# SCH_555-Circuit_2025-11-01.net
KiCad netlist of a schematic drawn in EasyEDA
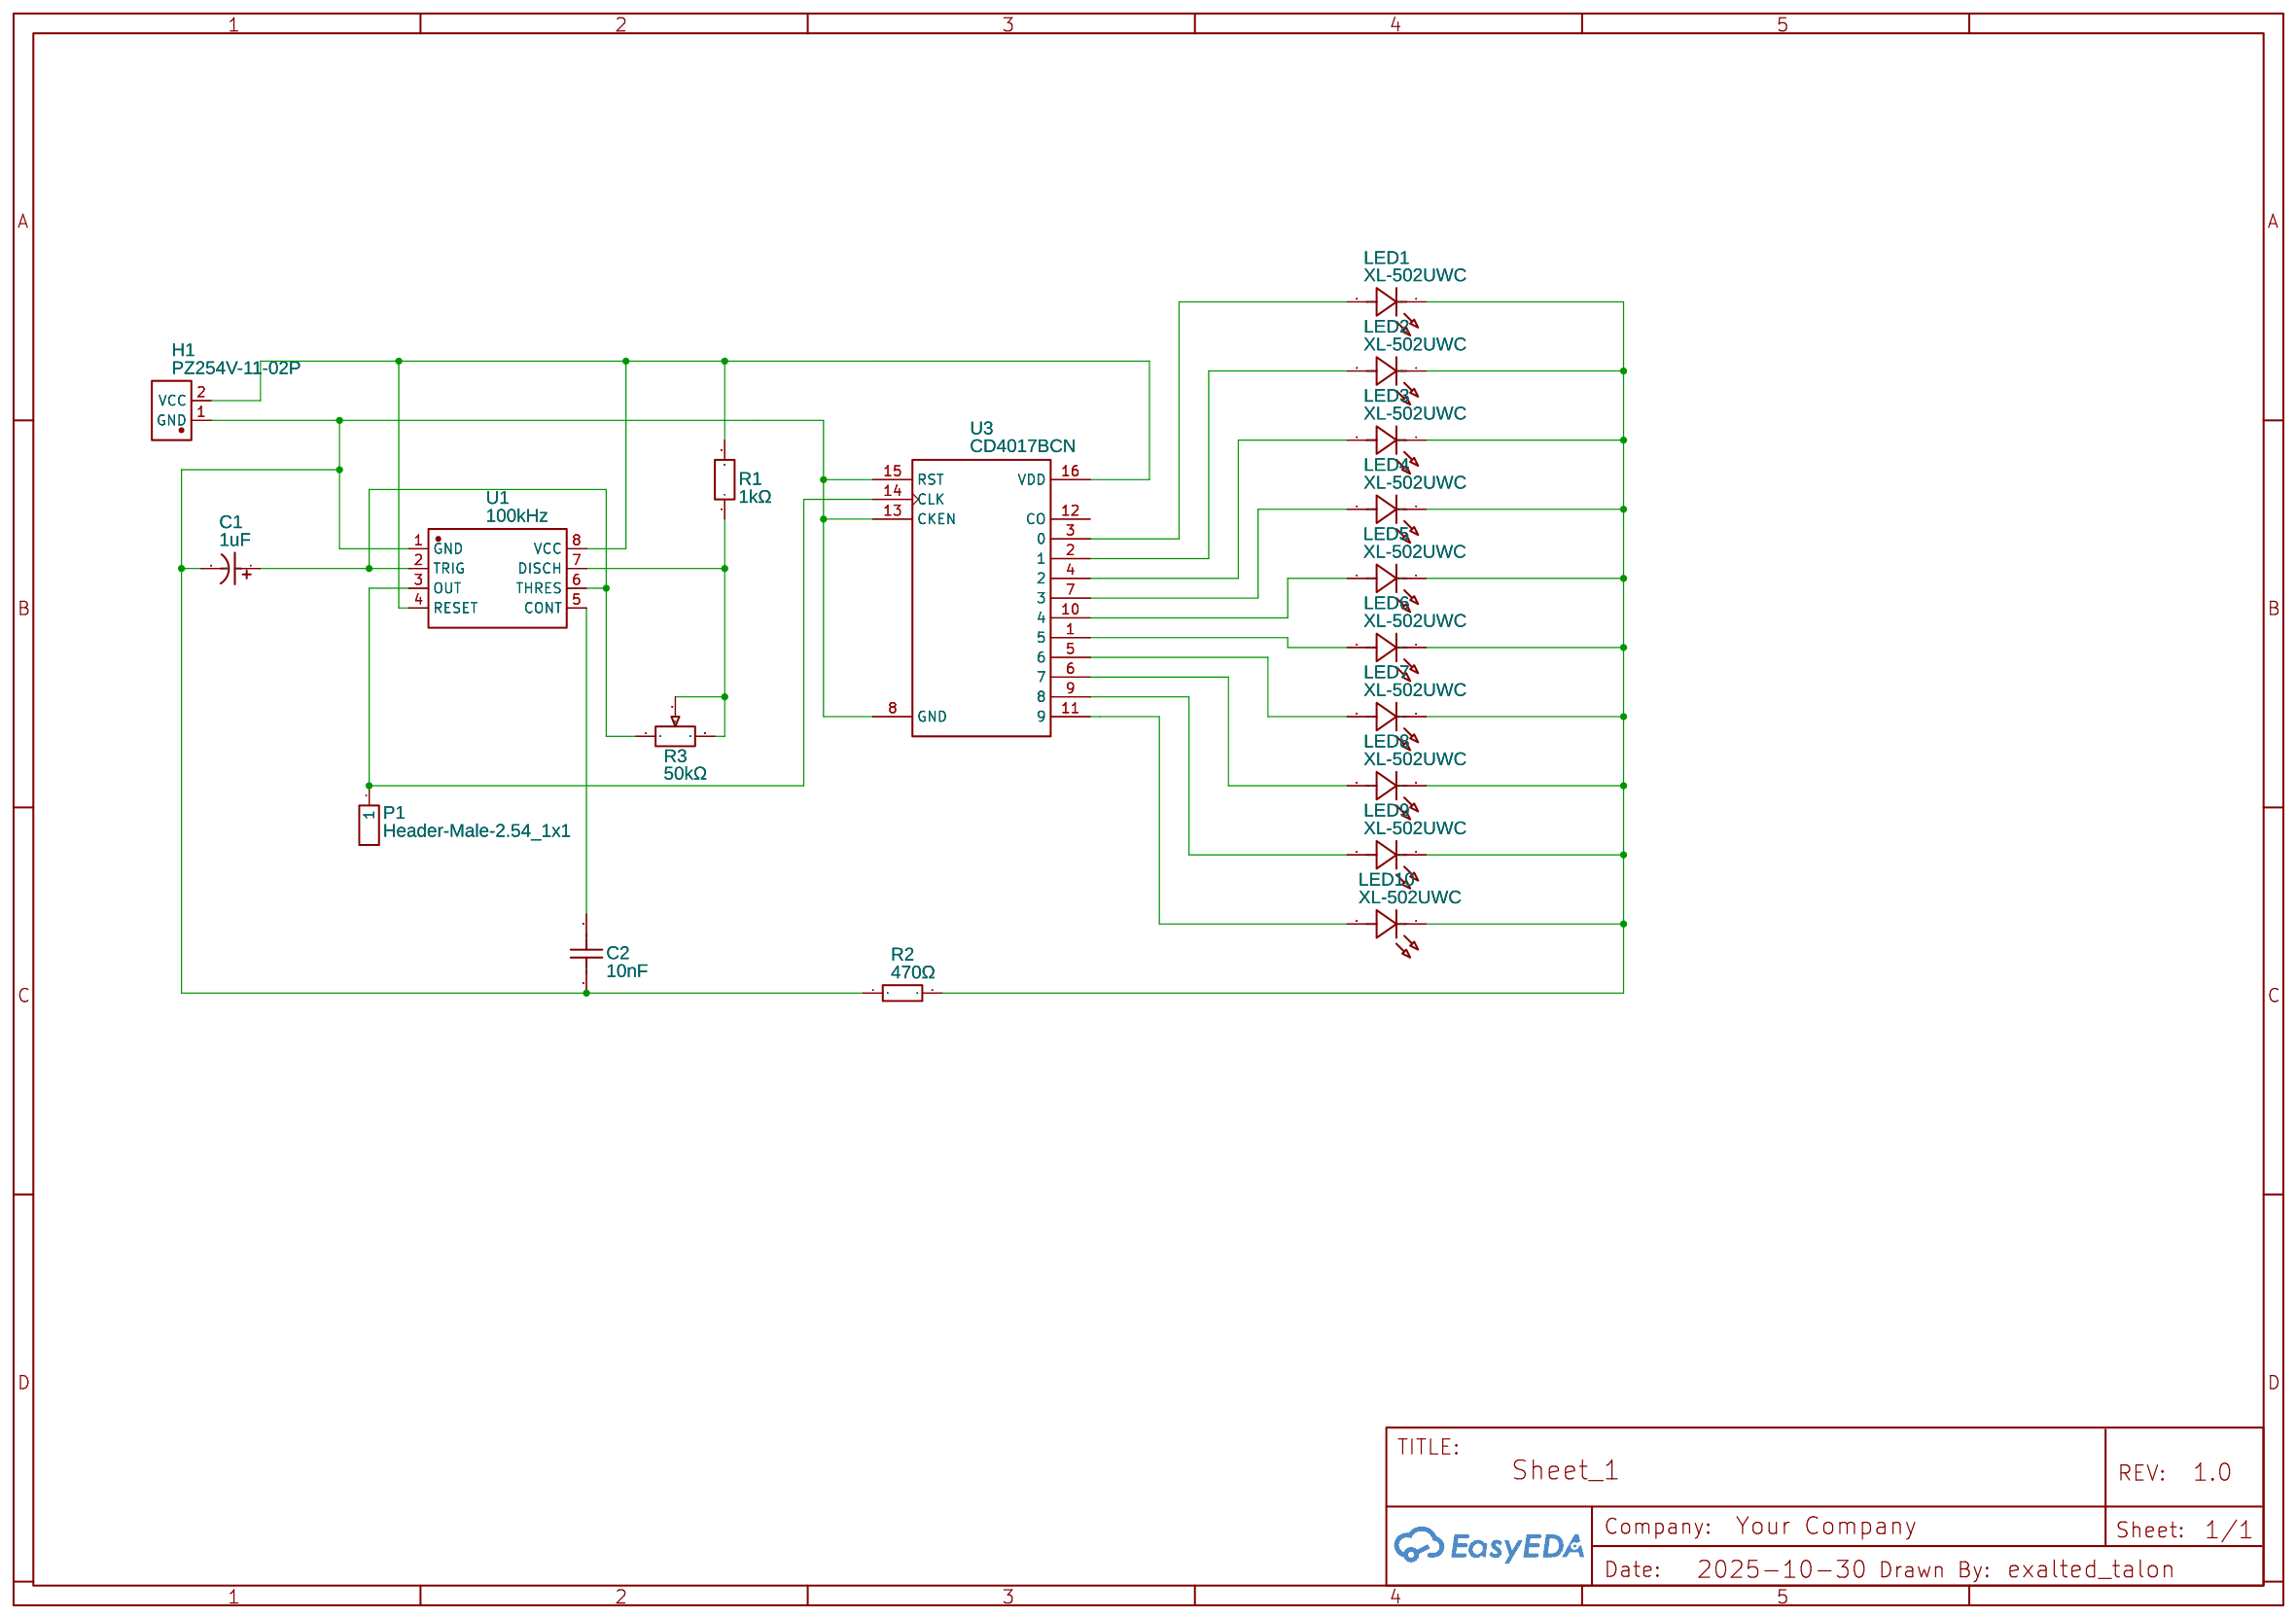
[diagram p0: schematic sheet]

(export (version "E")
  (design (tool "Eeschema 10.0.6"))
  (components
    (comp (ref "C1")
      (value "1uF")
      (fields (field (name "Manufacturer Part") "KF010M050C110A") (field (name "Manufacturer") "CapXon(丰宾)"))
      (libsource (lib "") (part "KF010M050C110A"))
    )
    (comp (ref "C2")
      (value "10nF")
      (fields (field (name "Manufacturer Part") "N09F1B103MN0B0S0N0") (field (name "Manufacturer") "STE(松田)"))
      (libsource (lib "") (part "N09F1B103MN0B0S0N0"))
    )
    (comp (ref "H1")
      (value "PZ254V-11-02P")
      (fields (field (name "Manufacturer") "XFCN(兴飞)"))
      (libsource (lib "") (part "PZ254V-11-02P"))
    )
    (comp (ref "LED1")
      (value "XL-502UWC")
      (fields (field (name "Manufacturer") "XINGLIGHT(成兴光)"))
      (libsource (lib "") (part "XL-502UWC"))
    )
    (comp (ref "LED2")
      (value "XL-502UWC")
      (fields (field (name "Manufacturer") "XINGLIGHT(成兴光)"))
      (libsource (lib "") (part "XL-502UWC"))
    )
    (comp (ref "LED3")
      (value "XL-502UWC")
      (fields (field (name "Manufacturer") "XINGLIGHT(成兴光)"))
      (libsource (lib "") (part "XL-502UWC"))
    )
    (comp (ref "LED4")
      (value "XL-502UWC")
      (fields (field (name "Manufacturer") "XINGLIGHT(成兴光)"))
      (libsource (lib "") (part "XL-502UWC"))
    )
    (comp (ref "LED5")
      (value "XL-502UWC")
      (fields (field (name "Manufacturer") "XINGLIGHT(成兴光)"))
      (libsource (lib "") (part "XL-502UWC"))
    )
    (comp (ref "LED6")
      (value "XL-502UWC")
      (fields (field (name "Manufacturer") "XINGLIGHT(成兴光)"))
      (libsource (lib "") (part "XL-502UWC"))
    )
    (comp (ref "LED7")
      (value "XL-502UWC")
      (fields (field (name "Manufacturer") "XINGLIGHT(成兴光)"))
      (libsource (lib "") (part "XL-502UWC"))
    )
    (comp (ref "LED8")
      (value "XL-502UWC")
      (fields (field (name "Manufacturer") "XINGLIGHT(成兴光)"))
      (libsource (lib "") (part "XL-502UWC"))
    )
    (comp (ref "LED9")
      (value "XL-502UWC")
      (fields (field (name "Manufacturer") "XINGLIGHT(成兴光)"))
      (libsource (lib "") (part "XL-502UWC"))
    )
    (comp (ref "LED10")
      (value "XL-502UWC")
      (fields (field (name "Manufacturer") "XINGLIGHT(成兴光)"))
      (libsource (lib "") (part "XL-502UWC"))
    )
    (comp (ref "P1")
      (value "Header-Male-2.54_1x1")
      (fields (field (name "Manufacturer Part") "2.54-1*1P针") (field (name "Manufacturer") "BOOMELE(博穆精密)"))
      (libsource (lib "") (part "Header-Male-2.54_1x1"))
    )
    (comp (ref "R1")
      (value "1kΩ")
      (fields (field (name "Manufacturer Part") "MF1/4W-1KΩ±1%T52") (field (name "Manufacturer") "华星机电"))
      (libsource (lib "") (part "MF1/4W-1KΩ±1%T52"))
    )
    (comp (ref "R2")
      (value "470Ω")
      (fields
        (field (name "Manufacturer Part") "MFR0W4F4700A50")
        (field (name "Manufacturer") "UNI-ROYAL(厚声)")
      )
      (libsource (lib "") (part "MFR0W4F4700A50"))
    )
    (comp (ref "R3")
      (value "50kΩ")
      (fields (field (name "Manufacturer Part") "3296X-1-503") (field (name "Manufacturer") "BOCHEN(博晨)"))
      (libsource (lib "") (part "3296X-1-503_C118912"))
    )
    (comp (ref "U1")
      (value "100kHz")
      (fields (field (name "Manufacturer Part") "NE555P") (field (name "Manufacturer") "TI(德州仪器)"))
      (libsource (lib "") (part "NE555P"))
    )
    (comp (ref "U3") (value "CD4017BCN") (libsource (lib "") (part "CD4017BCN")))
  )
  (nets
    (net (code "1") (name "Net-(H1-GND)") (class "Default")
      (node (ref "C1") (pin "2") (pinfunction "2_2") (pintype "input"))
      (node (ref "C2") (pin "1") (pinfunction "1_1") (pintype "unspecified"))
      (node (ref "H1") (pin "1") (pinfunction "GND_1") (pintype "unspecified"))
      (node (ref "R2") (pin "1") (pinfunction "1_1") (pintype "input"))
      (node (ref "U1") (pin "1") (pinfunction "GND_1") (pintype "unspecified"))
      (node (ref "U3") (pin "13") (pinfunction "CKEN_13") (pintype "unspecified"))
      (node (ref "U3") (pin "15") (pinfunction "RST_15") (pintype "unspecified"))
      (node (ref "U3") (pin "8") (pinfunction "GND_8") (pintype "passive"))
    )
    (net (code "2") (name "Net-(H1-VCC)") (class "Default")
      (node (ref "H1") (pin "2") (pinfunction "VCC_2") (pintype "unspecified"))
      (node (ref "R1") (pin "2") (pinfunction "2_2") (pintype "unspecified"))
      (node (ref "U1") (pin "4") (pinfunction "RESET_4") (pintype "unspecified"))
      (node (ref "U1") (pin "8") (pinfunction "VCC_8") (pintype "unspecified"))
      (node (ref "U3") (pin "16") (pinfunction "VDD_16") (pintype "passive"))
    )
    (net (code "3") (name "Net-(LED1-A)") (class "Default")
      (node (ref "LED1") (pin "2") (pinfunction "A_2") (pintype "unspecified"))
      (node (ref "U3") (pin "3") (pinfunction "0_3") (pintype "output"))
    )
    (net (code "4") (name "Net-(LED1-K)") (class "Default")
      (node (ref "LED1") (pin "1") (pinfunction "K_1") (pintype "unspecified"))
      (node (ref "LED10") (pin "1") (pinfunction "K_1") (pintype "unspecified"))
      (node (ref "LED2") (pin "1") (pinfunction "K_1") (pintype "unspecified"))
      (node (ref "LED3") (pin "1") (pinfunction "K_1") (pintype "unspecified"))
      (node (ref "LED4") (pin "1") (pinfunction "K_1") (pintype "unspecified"))
      (node (ref "LED5") (pin "1") (pinfunction "K_1") (pintype "unspecified"))
      (node (ref "LED6") (pin "1") (pinfunction "K_1") (pintype "unspecified"))
      (node (ref "LED7") (pin "1") (pinfunction "K_1") (pintype "unspecified"))
      (node (ref "LED8") (pin "1") (pinfunction "K_1") (pintype "unspecified"))
      (node (ref "LED9") (pin "1") (pinfunction "K_1") (pintype "unspecified"))
      (node (ref "R2") (pin "2") (pinfunction "2_2") (pintype "input"))
    )
    (net (code "5") (name "Net-(LED2-A)") (class "Default")
      (node (ref "LED2") (pin "2") (pinfunction "A_2") (pintype "unspecified"))
      (node (ref "U3") (pin "2") (pinfunction "1_2") (pintype "output"))
    )
    (net (code "6") (name "Net-(LED3-A)") (class "Default")
      (node (ref "LED3") (pin "2") (pinfunction "A_2") (pintype "unspecified"))
      (node (ref "U3") (pin "4") (pinfunction "2_4") (pintype "output"))
    )
    (net (code "7") (name "Net-(LED4-A)") (class "Default")
      (node (ref "LED4") (pin "2") (pinfunction "A_2") (pintype "unspecified"))
      (node (ref "U3") (pin "7") (pinfunction "3_7") (pintype "output"))
    )
    (net (code "8") (name "Net-(LED5-A)") (class "Default")
      (node (ref "LED5") (pin "2") (pinfunction "A_2") (pintype "unspecified"))
      (node (ref "U3") (pin "10") (pinfunction "4_10") (pintype "output"))
    )
    (net (code "9") (name "Net-(LED6-A)") (class "Default")
      (node (ref "LED6") (pin "2") (pinfunction "A_2") (pintype "unspecified"))
      (node (ref "U3") (pin "1") (pinfunction "5_1") (pintype "output"))
    )
    (net (code "10") (name "Net-(LED7-A)") (class "Default")
      (node (ref "LED7") (pin "2") (pinfunction "A_2") (pintype "unspecified"))
      (node (ref "U3") (pin "5") (pinfunction "6_5") (pintype "output"))
    )
    (net (code "11") (name "Net-(LED8-A)") (class "Default")
      (node (ref "LED8") (pin "2") (pinfunction "A_2") (pintype "unspecified"))
      (node (ref "U3") (pin "6") (pinfunction "7_6") (pintype "output"))
    )
    (net (code "12") (name "Net-(LED9-A)") (class "Default")
      (node (ref "LED9") (pin "2") (pinfunction "A_2") (pintype "unspecified"))
      (node (ref "U3") (pin "9") (pinfunction "8_9") (pintype "output"))
    )
    (net (code "13") (name "Net-(LED10-A)") (class "Default")
      (node (ref "LED10") (pin "2") (pinfunction "A_2") (pintype "unspecified"))
      (node (ref "U3") (pin "11") (pinfunction "9_11") (pintype "output"))
    )
    (net (code "14") (name "Net-(U1-CONT)") (class "Default")
      (node (ref "C2") (pin "2") (pinfunction "2_2") (pintype "unspecified"))
      (node (ref "U1") (pin "5") (pinfunction "CONT_5") (pintype "unspecified"))
    )
    (net (code "15") (name "Net-(U1-DISCH)") (class "Default")
      (node (ref "R1") (pin "1") (pinfunction "1_1") (pintype "unspecified"))
      (node (ref "R3") (pin "2") (pinfunction "2_2") (pintype "input"))
      (node (ref "R3") (pin "3") (pinfunction "3_3") (pintype "input"))
      (node (ref "U1") (pin "7") (pinfunction "DISCH_7") (pintype "unspecified"))
    )
    (net (code "16") (name "Net-(U1-OUT)") (class "Default")
      (node (ref "P1") (pin "1") (pinfunction "1_1") (pintype "input"))
      (node (ref "U1") (pin "3") (pinfunction "OUT_3") (pintype "unspecified"))
      (node (ref "U3") (pin "14") (pinfunction "CLK_14") (pintype "unspecified"))
    )
    (net (code "17") (name "Net-(U1-THRES)") (class "Default")
      (node (ref "C1") (pin "1") (pinfunction "1_1") (pintype "input"))
      (node (ref "R3") (pin "1") (pinfunction "1_1") (pintype "input"))
      (node (ref "U1") (pin "2") (pinfunction "TRIG_2") (pintype "unspecified"))
      (node (ref "U1") (pin "6") (pinfunction "THRES_6") (pintype "unspecified"))
    )
    (net (code "18") (name "unconnected-(U3-CO-Pad12)") (class "Default")
      (node (ref "U3") (pin "12") (pinfunction "CO_12") (pintype "output"))
    )
  )
)
